# Sheet1.net
KiCad netlist of a schematic drawn in Altium Designer
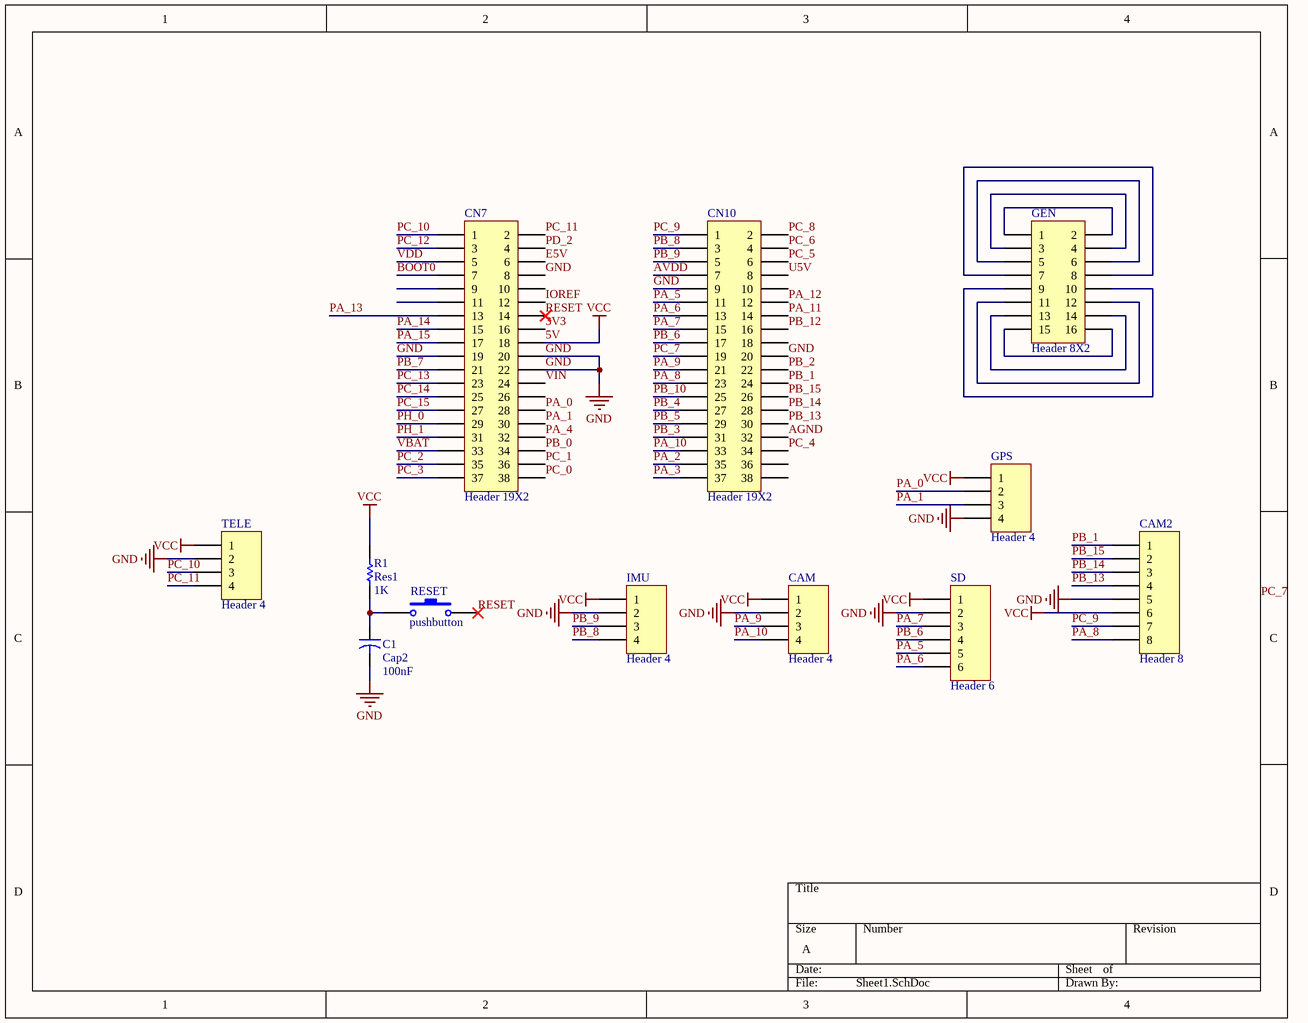
[diagram p0: Sheet1.SchDoc]

(export (version "E")
  (design (tool "Eeschema 10.0.6"))
  (components
    (comp (ref "C1")
      (value "Cap2")
      (footprint "CAPR5-4X5")
      (description "Capacitor")
      (fields (field (name "ALTIUM_VALUE") "100nF") (field (name "PUBLISHER") "Altium Limited"))
      (libsource (lib "Miscellaneous Devices") (part "Cap2"))
    )
    (comp (ref "CAM")
      (value "Header 4")
      (footprint "HDR1X4")
      (description "Header, 4-Pin")
      (fields (field (name "PUBLISHER") "Altium Limited"))
      (libsource (lib "Miscellaneous Connectors") (part "Header 4"))
    )
    (comp (ref "CAM2")
      (value "Header 8")
      (footprint "HDR1X8")
      (description "Header, 8-Pin")
      (fields (field (name "PUBLISHER") "Altium Limited"))
      (libsource (lib "Miscellaneous Connectors") (part "Header 8"))
    )
    (comp (ref "CN7")
      (value "Header 19X2")
      (footprint "HDR2X19")
      (description "Header, 19-Pin, Dual row")
      (fields (field (name "PUBLISHER") "Altium Limited"))
      (libsource (lib "Miscellaneous Connectors") (part "Header 19X2"))
    )
    (comp (ref "CN10")
      (value "Header 19X2")
      (footprint "HDR2X19")
      (description "Header, 19-Pin, Dual row")
      (fields (field (name "PUBLISHER") "Altium Limited"))
      (libsource (lib "Miscellaneous Connectors") (part "Header 19X2"))
    )
    (comp (ref "GEN")
      (value "Header 8X2")
      (footprint "HDR2X8")
      (description "Header, 8-Pin, Dual row")
      (fields (field (name "PUBLISHER") "Altium Limited"))
      (libsource (lib "Miscellaneous Connectors") (part "Header 8X2"))
    )
    (comp (ref "GPS")
      (value "Header 4")
      (footprint "HDR1X4")
      (description "Header, 4-Pin")
      (fields (field (name "PUBLISHER") "Altium Limited"))
      (libsource (lib "Miscellaneous Connectors") (part "Header 4"))
    )
    (comp (ref "IMU")
      (value "Header 4")
      (footprint "HDR1X4")
      (description "Header, 4-Pin")
      (fields (field (name "PUBLISHER") "Altium Limited"))
      (libsource (lib "Miscellaneous Connectors") (part "Header 4"))
    )
    (comp (ref "R1")
      (value "Res1")
      (footprint "AXIAL-0.3")
      (description "Resistor")
      (fields (field (name "ALTIUM_VALUE") "1K") (field (name "PUBLISHER") "Altium Limited"))
      (libsource (lib "Miscellaneous Devices") (part "Res1"))
    )
    (comp (ref "RESET")
      (value "pushbutton")
      (footprint "pushbutton")
      (libsource (lib "agfa other components") (part "pushbutton"))
    )
    (comp (ref "SD")
      (value "Header 6")
      (footprint "HDR1X6")
      (description "Header, 6-Pin")
      (fields (field (name "PUBLISHER") "Altium Limited"))
      (libsource (lib "Miscellaneous Connectors") (part "Header 6"))
    )
    (comp (ref "TELE")
      (value "Header 4")
      (footprint "HDR1X4")
      (description "Header, 4-Pin")
      (fields (field (name "PUBLISHER") "Altium Limited"))
      (libsource (lib "Miscellaneous Connectors") (part "Header 4"))
    )
  )
  (nets
    (net (code "1") (name "/3V3") (class "Default")
      (node (ref "CN7") (pin "16") (pinfunction "16_16") (pintype "passive"))
    )
    (net (code "2") (name "/AGND") (class "Default")
      (node (ref "CN10") (pin "32") (pinfunction "32_32") (pintype "passive"))
    )
    (net (code "3") (name "/AVDD") (class "Default")
      (node (ref "CN10") (pin "7") (pinfunction "7_7") (pintype "passive"))
    )
    (net (code "4") (name "/BOOT0") (class "Default")
      (node (ref "CN7") (pin "7") (pinfunction "7_7") (pintype "passive"))
    )
    (net (code "5") (name "/E5V") (class "Default")
      (node (ref "CN7") (pin "6") (pinfunction "6_6") (pintype "passive"))
    )
    (net (code "6") (name "/IOREF") (class "Default")
      (node (ref "CN7") (pin "12") (pinfunction "12_12") (pintype "passive"))
    )
    (net (code "7") (name "/PA_0") (class "Default")
      (node (ref "CN7") (pin "28") (pinfunction "28_28") (pintype "passive"))
      (node (ref "GPS") (pin "2") (pinfunction "2_2") (pintype "passive"))
    )
    (net (code "8") (name "/PA_1") (class "Default")
      (node (ref "CN7") (pin "30") (pinfunction "30_30") (pintype "passive"))
      (node (ref "GPS") (pin "3") (pinfunction "3_3") (pintype "passive"))
    )
    (net (code "9") (name "/PA_2") (class "Default")
      (node (ref "CN10") (pin "35") (pinfunction "35_35") (pintype "passive"))
    )
    (net (code "10") (name "/PA_3") (class "Default")
      (node (ref "CN10") (pin "37") (pinfunction "37_37") (pintype "passive"))
    )
    (net (code "11") (name "/PA_4") (class "Default")
      (node (ref "CN7") (pin "32") (pinfunction "32_32") (pintype "passive"))
    )
    (net (code "12") (name "/PA_5") (class "Default")
      (node (ref "CN10") (pin "11") (pinfunction "11_11") (pintype "passive"))
      (node (ref "SD") (pin "5") (pinfunction "5_5") (pintype "passive"))
    )
    (net (code "13") (name "/PA_6") (class "Default")
      (node (ref "CN10") (pin "13") (pinfunction "13_13") (pintype "passive"))
      (node (ref "SD") (pin "6") (pinfunction "6_6") (pintype "passive"))
    )
    (net (code "14") (name "/PA_7") (class "Default")
      (node (ref "CN10") (pin "15") (pinfunction "15_15") (pintype "passive"))
      (node (ref "SD") (pin "3") (pinfunction "3_3") (pintype "passive"))
    )
    (net (code "15") (name "/PA_8") (class "Default")
      (node (ref "CAM2") (pin "8") (pinfunction "8_8") (pintype "passive"))
      (node (ref "CN10") (pin "23") (pinfunction "23_23") (pintype "passive"))
    )
    (net (code "16") (name "/PA_9") (class "Default")
      (node (ref "CAM") (pin "3") (pinfunction "3_3") (pintype "passive"))
      (node (ref "CN10") (pin "21") (pinfunction "21_21") (pintype "passive"))
    )
    (net (code "17") (name "/PA_10") (class "Default")
      (node (ref "CAM") (pin "4") (pinfunction "4_4") (pintype "passive"))
      (node (ref "CN10") (pin "33") (pinfunction "33_33") (pintype "passive"))
    )
    (net (code "18") (name "/PA_11") (class "Default")
      (node (ref "CN10") (pin "14") (pinfunction "14_14") (pintype "passive"))
    )
    (net (code "19") (name "/PA_12") (class "Default")
      (node (ref "CN10") (pin "12") (pinfunction "12_12") (pintype "passive"))
    )
    (net (code "20") (name "/PA_13") (class "Default")
      (node (ref "CN7") (pin "13") (pinfunction "13_13") (pintype "passive"))
    )
    (net (code "21") (name "/PA_14") (class "Default")
      (node (ref "CN7") (pin "15") (pinfunction "15_15") (pintype "passive"))
    )
    (net (code "22") (name "/PA_15") (class "Default")
      (node (ref "CN7") (pin "17") (pinfunction "17_17") (pintype "passive"))
    )
    (net (code "23") (name "/PB_0") (class "Default")
      (node (ref "CN7") (pin "34") (pinfunction "34_34") (pintype "passive"))
    )
    (net (code "24") (name "/PB_1") (class "Default")
      (node (ref "CAM2") (pin "1") (pinfunction "1_1") (pintype "passive"))
      (node (ref "CN10") (pin "24") (pinfunction "24_24") (pintype "passive"))
    )
    (net (code "25") (name "/PB_2") (class "Default")
      (node (ref "CN10") (pin "22") (pinfunction "22_22") (pintype "passive"))
    )
    (net (code "26") (name "/PB_3") (class "Default")
      (node (ref "CN10") (pin "31") (pinfunction "31_31") (pintype "passive"))
    )
    (net (code "27") (name "/PB_4") (class "Default")
      (node (ref "CN10") (pin "27") (pinfunction "27_27") (pintype "passive"))
    )
    (net (code "28") (name "/PB_5") (class "Default")
      (node (ref "CN10") (pin "29") (pinfunction "29_29") (pintype "passive"))
    )
    (net (code "29") (name "/PB_6") (class "Default")
      (node (ref "CN10") (pin "17") (pinfunction "17_17") (pintype "passive"))
      (node (ref "SD") (pin "4") (pinfunction "4_4") (pintype "passive"))
    )
    (net (code "30") (name "/PB_7") (class "Default")
      (node (ref "CN7") (pin "21") (pinfunction "21_21") (pintype "passive"))
    )
    (net (code "31") (name "/PB_8") (class "Default")
      (node (ref "CN10") (pin "3") (pinfunction "3_3") (pintype "passive"))
      (node (ref "IMU") (pin "4") (pinfunction "4_4") (pintype "passive"))
    )
    (net (code "32") (name "/PB_9") (class "Default")
      (node (ref "CN10") (pin "5") (pinfunction "5_5") (pintype "passive"))
      (node (ref "IMU") (pin "3") (pinfunction "3_3") (pintype "passive"))
    )
    (net (code "33") (name "/PB_10") (class "Default")
      (node (ref "CN10") (pin "25") (pinfunction "25_25") (pintype "passive"))
    )
    (net (code "34") (name "/PB_12") (class "Default")
      (node (ref "CN10") (pin "16") (pinfunction "16_16") (pintype "passive"))
    )
    (net (code "35") (name "/PB_13") (class "Default")
      (node (ref "CAM2") (pin "4") (pinfunction "4_4") (pintype "passive"))
      (node (ref "CN10") (pin "30") (pinfunction "30_30") (pintype "passive"))
    )
    (net (code "36") (name "/PB_14") (class "Default")
      (node (ref "CAM2") (pin "3") (pinfunction "3_3") (pintype "passive"))
      (node (ref "CN10") (pin "28") (pinfunction "28_28") (pintype "passive"))
    )
    (net (code "37") (name "/PB_15") (class "Default")
      (node (ref "CAM2") (pin "2") (pinfunction "2_2") (pintype "passive"))
      (node (ref "CN10") (pin "26") (pinfunction "26_26") (pintype "passive"))
    )
    (net (code "38") (name "/PC_0") (class "Default")
      (node (ref "CN7") (pin "38") (pinfunction "38_38") (pintype "passive"))
    )
    (net (code "39") (name "/PC_1") (class "Default")
      (node (ref "CN7") (pin "36") (pinfunction "36_36") (pintype "passive"))
    )
    (net (code "40") (name "/PC_2") (class "Default")
      (node (ref "CN7") (pin "35") (pinfunction "35_35") (pintype "passive"))
    )
    (net (code "41") (name "/PC_3") (class "Default")
      (node (ref "CN7") (pin "37") (pinfunction "37_37") (pintype "passive"))
    )
    (net (code "42") (name "/PC_4") (class "Default")
      (node (ref "CN10") (pin "34") (pinfunction "34_34") (pintype "passive"))
    )
    (net (code "43") (name "/PC_5") (class "Default")
      (node (ref "CN10") (pin "6") (pinfunction "6_6") (pintype "passive"))
    )
    (net (code "44") (name "/PC_6") (class "Default")
      (node (ref "CN10") (pin "4") (pinfunction "4_4") (pintype "passive"))
    )
    (net (code "45") (name "/PC_7") (class "Default")
      (node (ref "CN10") (pin "19") (pinfunction "19_19") (pintype "passive"))
    )
    (net (code "46") (name "/PC_8") (class "Default")
      (node (ref "CN10") (pin "2") (pinfunction "2_2") (pintype "passive"))
    )
    (net (code "47") (name "/PC_9") (class "Default")
      (node (ref "CAM2") (pin "7") (pinfunction "7_7") (pintype "passive"))
      (node (ref "CN10") (pin "1") (pinfunction "1_1") (pintype "passive"))
    )
    (net (code "48") (name "/PC_10") (class "Default")
      (node (ref "CN7") (pin "1") (pinfunction "1_1") (pintype "passive"))
      (node (ref "TELE") (pin "3") (pinfunction "3_3") (pintype "passive"))
    )
    (net (code "49") (name "/PC_11") (class "Default")
      (node (ref "CN7") (pin "2") (pinfunction "2_2") (pintype "passive"))
      (node (ref "TELE") (pin "4") (pinfunction "4_4") (pintype "passive"))
    )
    (net (code "50") (name "/PC_12") (class "Default")
      (node (ref "CN7") (pin "3") (pinfunction "3_3") (pintype "passive"))
    )
    (net (code "51") (name "/PC_13") (class "Default")
      (node (ref "CN7") (pin "23") (pinfunction "23_23") (pintype "passive"))
    )
    (net (code "52") (name "/PC_14") (class "Default")
      (node (ref "CN7") (pin "25") (pinfunction "25_25") (pintype "passive"))
    )
    (net (code "53") (name "/PC_15") (class "Default")
      (node (ref "CN7") (pin "27") (pinfunction "27_27") (pintype "passive"))
    )
    (net (code "54") (name "/PD_2") (class "Default")
      (node (ref "CN7") (pin "4") (pinfunction "4_4") (pintype "passive"))
    )
    (net (code "55") (name "/PH_0") (class "Default")
      (node (ref "CN7") (pin "29") (pinfunction "29_29") (pintype "passive"))
    )
    (net (code "56") (name "/PH_1") (class "Default")
      (node (ref "CN7") (pin "31") (pinfunction "31_31") (pintype "passive"))
    )
    (net (code "57") (name "/RESET") (class "Default")
      (node (ref "CN7") (pin "14") (pinfunction "14_14") (pintype "passive"))
      (node (ref "RESET") (pin "2") (pinfunction "2_2") (pintype "passive"))
    )
    (net (code "58") (name "/U5V") (class "Default")
      (node (ref "CN10") (pin "8") (pinfunction "8_8") (pintype "passive"))
    )
    (net (code "59") (name "/VBAT") (class "Default")
      (node (ref "CN7") (pin "33") (pinfunction "33_33") (pintype "passive"))
    )
    (net (code "60") (name "/VDD") (class "Default")
      (node (ref "CN7") (pin "5") (pinfunction "5_5") (pintype "passive"))
    )
    (net (code "61") (name "/VIN") (class "Default")
      (node (ref "CN7") (pin "24") (pinfunction "24_24") (pintype "passive"))
    )
    (net (code "62") (name "GND") (class "Default")
      (node (ref "C1") (pin "2") (pinfunction "2_2") (pintype "passive"))
      (node (ref "CAM") (pin "2") (pinfunction "2_2") (pintype "passive"))
      (node (ref "CAM2") (pin "5") (pinfunction "5_5") (pintype "passive"))
      (node (ref "CN10") (pin "20") (pinfunction "20_20") (pintype "passive"))
      (node (ref "CN10") (pin "9") (pinfunction "9_9") (pintype "passive"))
      (node (ref "CN7") (pin "19") (pinfunction "19_19") (pintype "passive"))
      (node (ref "CN7") (pin "20") (pinfunction "20_20") (pintype "passive"))
      (node (ref "CN7") (pin "22") (pinfunction "22_22") (pintype "passive"))
      (node (ref "CN7") (pin "8") (pinfunction "8_8") (pintype "passive"))
      (node (ref "GPS") (pin "4") (pinfunction "4_4") (pintype "passive"))
      (node (ref "IMU") (pin "2") (pinfunction "2_2") (pintype "passive"))
      (node (ref "SD") (pin "2") (pinfunction "2_2") (pintype "passive"))
      (node (ref "TELE") (pin "2") (pinfunction "2_2") (pintype "passive"))
    )
    (net (code "63") (name "Net-(C1-Pad1)") (class "Default")
      (node (ref "C1") (pin "1") (pinfunction "1_1") (pintype "passive"))
      (node (ref "R1") (pin "1") (pinfunction "1_1") (pintype "passive"))
      (node (ref "RESET") (pin "1") (pinfunction "1_1") (pintype "passive"))
    )
    (net (code "64") (name "Net-(GEN-Pad1)") (class "Default")
      (node (ref "GEN") (pin "1") (pinfunction "1_1") (pintype "passive"))
      (node (ref "GEN") (pin "2") (pinfunction "2_2") (pintype "passive"))
    )
    (net (code "65") (name "Net-(GEN-Pad3)") (class "Default")
      (node (ref "GEN") (pin "3") (pinfunction "3_3") (pintype "passive"))
      (node (ref "GEN") (pin "4") (pinfunction "4_4") (pintype "passive"))
    )
    (net (code "66") (name "Net-(GEN-Pad5)") (class "Default")
      (node (ref "GEN") (pin "5") (pinfunction "5_5") (pintype "passive"))
      (node (ref "GEN") (pin "6") (pinfunction "6_6") (pintype "passive"))
    )
    (net (code "67") (name "Net-(GEN-Pad7)") (class "Default")
      (node (ref "GEN") (pin "7") (pinfunction "7_7") (pintype "passive"))
      (node (ref "GEN") (pin "8") (pinfunction "8_8") (pintype "passive"))
    )
    (net (code "68") (name "Net-(GEN-Pad10)") (class "Default")
      (node (ref "GEN") (pin "10") (pinfunction "10_10") (pintype "passive"))
      (node (ref "GEN") (pin "9") (pinfunction "9_9") (pintype "passive"))
    )
    (net (code "69") (name "Net-(GEN-Pad11)") (class "Default")
      (node (ref "GEN") (pin "11") (pinfunction "11_11") (pintype "passive"))
      (node (ref "GEN") (pin "12") (pinfunction "12_12") (pintype "passive"))
    )
    (net (code "70") (name "Net-(GEN-Pad13)") (class "Default")
      (node (ref "GEN") (pin "13") (pinfunction "13_13") (pintype "passive"))
      (node (ref "GEN") (pin "14") (pinfunction "14_14") (pintype "passive"))
    )
    (net (code "71") (name "Net-(GEN-Pad15)") (class "Default")
      (node (ref "GEN") (pin "15") (pinfunction "15_15") (pintype "passive"))
      (node (ref "GEN") (pin "16") (pinfunction "16_16") (pintype "passive"))
    )
    (net (code "72") (name "VCC") (class "Default")
      (node (ref "CAM") (pin "1") (pinfunction "1_1") (pintype "passive"))
      (node (ref "CAM2") (pin "6") (pinfunction "6_6") (pintype "passive"))
      (node (ref "CN7") (pin "18") (pinfunction "18_18") (pintype "passive"))
      (node (ref "GPS") (pin "1") (pinfunction "1_1") (pintype "passive"))
      (node (ref "IMU") (pin "1") (pinfunction "1_1") (pintype "passive"))
      (node (ref "R1") (pin "2") (pinfunction "2_2") (pintype "passive"))
      (node (ref "SD") (pin "1") (pinfunction "1_1") (pintype "passive"))
      (node (ref "TELE") (pin "1") (pinfunction "1_1") (pintype "passive"))
    )
    (net (code "73") (name "unconnected-(CN7-Pad9)") (class "Default")
      (node (ref "CN7") (pin "9") (pinfunction "9_9") (pintype "passive"))
    )
    (net (code "74") (name "unconnected-(CN7-Pad10)") (class "Default")
      (node (ref "CN7") (pin "10") (pinfunction "10_10") (pintype "passive"))
    )
    (net (code "75") (name "unconnected-(CN7-Pad11)") (class "Default")
      (node (ref "CN7") (pin "11") (pinfunction "11_11") (pintype "passive"))
    )
    (net (code "76") (name "unconnected-(CN7-Pad26)") (class "Default")
      (node (ref "CN7") (pin "26") (pinfunction "26_26") (pintype "passive"))
    )
    (net (code "77") (name "unconnected-(CN10-Pad10)") (class "Default")
      (node (ref "CN10") (pin "10") (pinfunction "10_10") (pintype "passive"))
    )
    (net (code "78") (name "unconnected-(CN10-Pad18)") (class "Default")
      (node (ref "CN10") (pin "18") (pinfunction "18_18") (pintype "passive"))
    )
    (net (code "79") (name "unconnected-(CN10-Pad36)") (class "Default")
      (node (ref "CN10") (pin "36") (pinfunction "36_36") (pintype "passive"))
    )
    (net (code "80") (name "unconnected-(CN10-Pad38)") (class "Default")
      (node (ref "CN10") (pin "38") (pinfunction "38_38") (pintype "passive"))
    )
  )
)
